# charger_v3_1.net
KiCad netlist of a schematic drawn in EAGLE
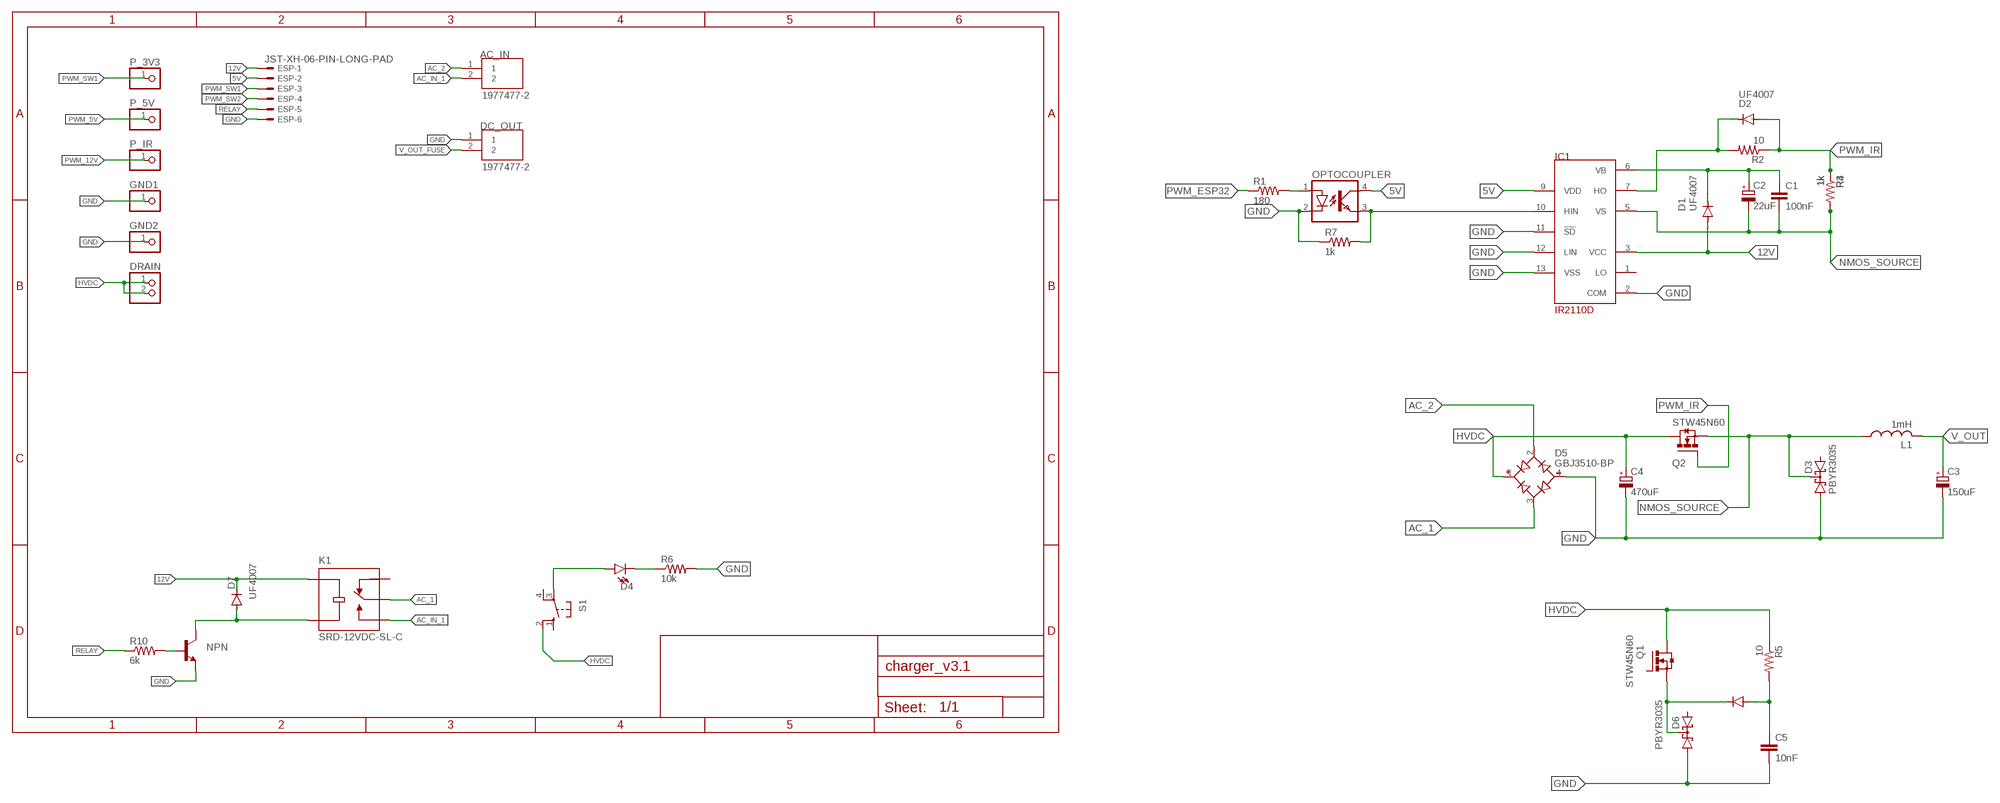
[diagram p0: schematic, sheet 1]

(export (version "E")
  (design (tool "Eeschema 10.0.6"))
  (components
    (comp (ref "AC_IN")
      (value "1977477-2")
      (footprint "eagle-import:TE_1977477-2")
      (fields (field (name "MF") "TE Connectivity"))
      (libsource (lib "eagle-import") (part "1977477-2"))
    )
    (comp (ref "C1")
      (value "100nF")
      (footprint "eagle-import:C025-025X050")
      (libsource (lib "eagle-import") (part "C-EU025-025X050"))
    )
    (comp (ref "C2")
      (value "22uF")
      (footprint "eagle-import:E2,5-6E")
      (libsource (lib "eagle-import") (part "CPOL-EUE2,5-6E"))
    )
    (comp (ref "C3")
      (value "150uF")
      (footprint "eagle-import:E7,5-18")
      (libsource (lib "eagle-import") (part "CPOL-EUE7.5-18"))
    )
    (comp (ref "C4")
      (value "470uF")
      (footprint "eagle-import:EB35D")
      (libsource (lib "eagle-import") (part "CPOL-EUE10-35"))
    )
    (comp (ref "C5")
      (value "10nF")
      (footprint "eagle-import:C025-025X050")
      (libsource (lib "eagle-import") (part "C-EU025-025X050"))
    )
    (comp (ref "D1")
      (value "UF4007")
      (footprint "eagle-import:DO34-7")
      (libsource (lib "eagle-import") (part "BAS15"))
    )
    (comp (ref "D2")
      (value "UF4007")
      (footprint "eagle-import:DO34-7")
      (libsource (lib "eagle-import") (part "BAS15"))
    )
    (comp (ref "D3")
      (value "PBYR3035")
      (footprint "eagle-import:SOT93S")
      (libsource (lib "eagle-import") (part "PBYR3035"))
    )
    (comp (ref "D4")
      (value "LED5MM")
      (footprint "eagle-import:LED_5MM")
      (libsource (lib "eagle-import") (part "LED5MM"))
    )
    (comp (ref "D5")
      (value "GBJ3510-BP")
      (footprint "eagle-import:DIOB_GBJ3510-BP")
      (fields (field (name "MF") "Micro Commercial"))
      (libsource (lib "eagle-import") (part "GBJ3510-BP"))
    )
    (comp (ref "D6")
      (value "PBYR3035")
      (footprint "eagle-import:SOT93S")
      (libsource (lib "eagle-import") (part "PBYR3035"))
    )
    (comp (ref "D7")
      (value "UF4007")
      (footprint "eagle-import:DO34-7")
      (libsource (lib "eagle-import") (part "BAS15"))
    )
    (comp (ref "D8")
      (value "1N4148DO35-7")
      (footprint "eagle-import:DO35-7")
      (libsource (lib "eagle-import") (part "1N4148DO35-7"))
    )
    (comp (ref "DC_OUT")
      (value "1977477-2")
      (footprint "eagle-import:TE_1977477-2")
      (fields (field (name "MF") "TE Connectivity"))
      (libsource (lib "eagle-import") (part "1977477-2"))
    )
    (comp (ref "DRAIN")
      (value "PINHD-1X2")
      (footprint "eagle-import:1X02")
      (libsource (lib "eagle-import") (part "PINHD-1X2"))
    )
    (comp (ref "ESP")
      (value "JST-XH-06-PIN-LONG-PAD")
      (footprint "eagle-import:JST-XH-06-PACKAGE-LONG-PAD")
      (libsource (lib "eagle-import") (part "JST-XH-06-PIN-LONG-PAD"))
    )
    (comp (ref "GND1")
      (value "PINHD-1X1")
      (footprint "eagle-import:1X01")
      (libsource (lib "eagle-import") (part "PINHD-1X1"))
    )
    (comp (ref "GND2")
      (value "PINHD-1X1")
      (footprint "eagle-import:1X01")
      (libsource (lib "eagle-import") (part "PINHD-1X1"))
    )
    (comp (ref "IC1")
      (value "IR2110D")
      (footprint "eagle-import:DIL14")
      (libsource (lib "eagle-import") (part "IR2110D"))
    )
    (comp (ref "K1")
      (value "SRD-12VDC-SL-C")
      (footprint "eagle-import:RELAY_SRD-12VDC-SL-C")
      (fields (field (name "MF") "Songle Relay"))
      (libsource (lib "eagle-import") (part "SRD-12VDC-SL-C"))
    )
    (comp (ref "L1")
      (value "1mH")
      (footprint "eagle-import:TJ7-U1")
      (libsource (lib "eagle-import") (part "L-USTJ7-U1"))
    )
    (comp (ref "NPN")
      (value "BC547A-NPN-TO92-CBE")
      (footprint "eagle-import:TO92-CBE")
      (libsource (lib "eagle-import") (part "-NPN-TO92-CBEBC547A"))
    )
    (comp (ref "OPTOCOUPLER")
      (value "SFH618A-5")
      (footprint "eagle-import:DIP4")
      (fields (field (name "MF") "VISHAY/TELEFUNKEN"))
      (libsource (lib "eagle-import") (part "SFH618?A-5"))
    )
    (comp (ref "P_3V3")
      (value "PINHD-1X1")
      (footprint "eagle-import:1X01")
      (libsource (lib "eagle-import") (part "PINHD-1X1"))
    )
    (comp (ref "P_5V")
      (value "PINHD-1X1")
      (footprint "eagle-import:1X01")
      (libsource (lib "eagle-import") (part "PINHD-1X1"))
    )
    (comp (ref "P_IR")
      (value "PINHD-1X1")
      (footprint "eagle-import:1X01")
      (libsource (lib "eagle-import") (part "PINHD-1X1"))
    )
    (comp (ref "Q1")
      (value "STW45N60")
      (footprint "eagle-import:TO247AC")
      (fields (field (name "MF") "Vishay Siliconix") (field (name "MP") "IRFP240"))
      (libsource (lib "eagle-import") (part "IRFP240"))
    )
    (comp (ref "Q2")
      (value "STW45N60")
      (footprint "eagle-import:TO247AC")
      (fields (field (name "MF") "Vishay Siliconix") (field (name "MP") "IRFP240"))
      (libsource (lib "eagle-import") (part "IRFP240"))
    )
    (comp (ref "R1")
      (value "180")
      (footprint "eagle-import:0204_7")
      (libsource (lib "eagle-import") (part "R-US_0204/7"))
    )
    (comp (ref "R2")
      (value "10")
      (footprint "eagle-import:0204_7")
      (libsource (lib "eagle-import") (part "R-US_0204/7"))
    )
    (comp (ref "R3")
      (value "1k")
      (footprint "eagle-import:0204_7")
      (libsource (lib "eagle-import") (part "R-US_0204/7"))
    )
    (comp (ref "R4")
      (value "1k")
      (footprint "eagle-import:0204_7")
      (libsource (lib "eagle-import") (part "R-US_0204/7"))
    )
    (comp (ref "R5")
      (value "10")
      (footprint "eagle-import:0204_7")
      (libsource (lib "eagle-import") (part "R-US_0204/7"))
    )
    (comp (ref "R6")
      (value "10k")
      (footprint "eagle-import:0204_7")
      (libsource (lib "eagle-import") (part "R-US_0204/7"))
    )
    (comp (ref "R7")
      (value "1k")
      (footprint "eagle-import:0204_7")
      (libsource (lib "eagle-import") (part "R-US_0204/7"))
    )
    (comp (ref "R10")
      (value "6k")
      (footprint "eagle-import:0204_7")
      (libsource (lib "eagle-import") (part "R-US_0204/7"))
    )
    (comp (ref "S1")
      (value "10-XX")
      (footprint "eagle-import:B3F-10XX")
      (fields (field (name "MPN") "B3F-1000"))
      (libsource (lib "eagle-import") (part "10-XX"))
    )
  )
  (nets
    (net (code "1") (name "5V") (class "Default")
      (node (ref "ESP") (pin "2") (pinfunction "S_2") (pintype "passive"))
      (node (ref "IC1") (pin "9") (pinfunction "VDD_9") (pintype "power_in"))
      (node (ref "OPTOCOUPLER") (pin "4") (pinfunction "COL_4") (pintype "passive"))
    )
    (net (code "2") (name "12V") (class "Default")
      (node (ref "D1") (pin "A") (pinfunction "A_A") (pintype "passive"))
      (node (ref "D7") (pin "C") (pinfunction "C_C") (pintype "passive"))
      (node (ref "ESP") (pin "1") (pinfunction "S_1") (pintype "passive"))
      (node (ref "IC1") (pin "3") (pinfunction "VCC_3") (pintype "power_in"))
      (node (ref "K1") (pin "COIL1") (pinfunction "COIL1_COIL1") (pintype "passive"))
    )
    (net (code "3") (name "AC_1") (class "Default")
      (node (ref "D5") (pin "3") (pinfunction "AC2_3") (pintype "passive"))
      (node (ref "K1") (pin "COM") (pinfunction "COM_COM") (pintype "passive"))
    )
    (net (code "4") (name "AC_2") (class "Default")
      (node (ref "AC_IN") (pin "1") (pinfunction "1_1") (pintype "passive"))
      (node (ref "D5") (pin "2") (pinfunction "AC1_2") (pintype "passive"))
    )
    (net (code "5") (name "AC_IN_1") (class "Default")
      (node (ref "AC_IN") (pin "2") (pinfunction "2_2") (pintype "passive"))
      (node (ref "K1") (pin "NO") (pinfunction "NO_NO") (pintype "passive"))
    )
    (net (code "6") (name "GND") (class "Default")
      (node (ref "C3") (pin "-") (pinfunction "-_-") (pintype "passive"))
      (node (ref "C4") (pin "-") (pinfunction "-_-") (pintype "passive"))
      (node (ref "D3") (pin "A1") (pinfunction "A1_A1") (pintype "passive"))
      (node (ref "D5") (pin "4") (pinfunction "-_4") (pintype "passive"))
      (node (ref "DC_OUT") (pin "1") (pinfunction "1_1") (pintype "passive"))
      (node (ref "ESP") (pin "6") (pinfunction "S_6") (pintype "passive"))
      (node (ref "GND1") (pin "1") (pinfunction "1_1") (pintype "passive"))
      (node (ref "GND2") (pin "1") (pinfunction "1_1") (pintype "passive"))
      (node (ref "IC1") (pin "11") (pinfunction "~{SD}_11") (pintype "input"))
      (node (ref "IC1") (pin "12") (pinfunction "LIN_12") (pintype "input"))
      (node (ref "IC1") (pin "13") (pinfunction "VSS_13") (pintype "power_in"))
      (node (ref "IC1") (pin "2") (pinfunction "COM_2") (pintype "power_in"))
      (node (ref "NPN") (pin "E") (pinfunction "E_E") (pintype "passive"))
      (node (ref "OPTOCOUPLER") (pin "2") (pinfunction "C_2") (pintype "passive"))
      (node (ref "R6") (pin "2") (pinfunction "2_2") (pintype "passive"))
      (node (ref "R7") (pin "1") (pinfunction "1_1") (pintype "passive"))
    )
    (net (code "7") (name "HVDC") (class "Default")
      (node (ref "C4") (pin "+") (pinfunction "+_+") (pintype "passive"))
      (node (ref "D5") (pin "1") (pinfunction "+_1") (pintype "passive"))
      (node (ref "DRAIN") (pin "1") (pinfunction "1_1") (pintype "passive"))
      (node (ref "DRAIN") (pin "2") (pinfunction "2_2") (pintype "passive"))
      (node (ref "Q2") (pin "2") (pinfunction "D_2") (pintype "passive"))
      (node (ref "S1") (pin "2") (pinfunction "S1_2") (pintype "passive"))
    )
    (net (code "8") (name "NMOS_SOURCE") (class "Default")
      (node (ref "C1") (pin "2") (pinfunction "2_2") (pintype "passive"))
      (node (ref "C2") (pin "-") (pinfunction "-_-") (pintype "passive"))
      (node (ref "D3") (pin "C") (pinfunction "C_C") (pintype "passive"))
      (node (ref "IC1") (pin "5") (pinfunction "VS_5") (pintype "power_in"))
      (node (ref "L1") (pin "1") (pinfunction "1_1") (pintype "passive"))
      (node (ref "Q2") (pin "3") (pinfunction "S_3") (pintype "passive"))
      (node (ref "R3") (pin "2") (pinfunction "2_2") (pintype "passive"))
      (node (ref "R4") (pin "2") (pinfunction "2_2") (pintype "passive"))
    )
    (net (code "9") (name "Net-(C5-Pad1)") (class "Default")
      (node (ref "C5") (pin "1") (pinfunction "1_1") (pintype "passive"))
      (node (ref "D8") (pin "A") (pinfunction "A_A") (pintype "passive"))
      (node (ref "R5") (pin "2") (pinfunction "2_2") (pintype "passive"))
    )
    (net (code "10") (name "Net-(C5-Pad2)") (class "Default")
      (node (ref "C5") (pin "2") (pinfunction "2_2") (pintype "passive"))
      (node (ref "D6") (pin "A1") (pinfunction "A1_A1") (pintype "passive"))
    )
    (net (code "11") (name "Net-(D4-C)") (class "Default")
      (node (ref "D4") (pin "K") (pinfunction "C_K") (pintype "passive"))
      (node (ref "R6") (pin "1") (pinfunction "1_1") (pintype "passive"))
    )
    (net (code "12") (name "Net-(D7-PadA)") (class "Default")
      (node (ref "D7") (pin "A") (pinfunction "A_A") (pintype "passive"))
      (node (ref "K1") (pin "COIL2") (pinfunction "COIL2_COIL2") (pintype "passive"))
      (node (ref "NPN") (pin "C") (pinfunction "C_C") (pintype "passive"))
    )
    (net (code "13") (name "Net-(IC1-HO)") (class "Default")
      (node (ref "D2") (pin "C") (pinfunction "C_C") (pintype "passive"))
      (node (ref "IC1") (pin "7") (pinfunction "HO_7") (pintype "output"))
      (node (ref "R2") (pin "2") (pinfunction "2_2") (pintype "passive"))
    )
    (net (code "14") (name "Net-(IC1-VB)") (class "Default")
      (node (ref "C1") (pin "1") (pinfunction "1_1") (pintype "passive"))
      (node (ref "C2") (pin "+") (pinfunction "+_+") (pintype "passive"))
      (node (ref "D1") (pin "C") (pinfunction "C_C") (pintype "passive"))
      (node (ref "IC1") (pin "6") (pinfunction "VB_6") (pintype "power_in"))
    )
    (net (code "15") (name "Net-(NPN-PadB)") (class "Default")
      (node (ref "NPN") (pin "B") (pinfunction "B_B") (pintype "passive"))
      (node (ref "R10") (pin "2") (pinfunction "2_2") (pintype "passive"))
    )
    (net (code "16") (name "Net-(OPTOCOUPLER-A)") (class "Default")
      (node (ref "OPTOCOUPLER") (pin "1") (pinfunction "A_1") (pintype "passive"))
      (node (ref "R1") (pin "2") (pinfunction "2_2") (pintype "passive"))
    )
    (net (code "17") (name "Net-(Q1-D)") (class "Default")
      (node (ref "Q1") (pin "2") (pinfunction "D_2") (pintype "passive"))
      (node (ref "R5") (pin "1") (pinfunction "1_1") (pintype "passive"))
    )
    (net (code "18") (name "Net-(Q1-S)") (class "Default")
      (node (ref "D6") (pin "C") (pinfunction "C_C") (pintype "passive"))
      (node (ref "D8") (pin "C") (pinfunction "C_C") (pintype "passive"))
      (node (ref "Q1") (pin "3") (pinfunction "S_3") (pintype "passive"))
    )
    (net (code "19") (name "Net-(S1-P)") (class "Default")
      (node (ref "D4") (pin "A") (pinfunction "A_A") (pintype "passive"))
      (node (ref "S1") (pin "3") (pinfunction "P_3") (pintype "passive"))
    )
    (net (code "20") (name "PWM_5V") (class "Default")
      (node (ref "IC1") (pin "10") (pinfunction "HIN_10") (pintype "input"))
      (node (ref "OPTOCOUPLER") (pin "3") (pinfunction "EMIT_3") (pintype "passive"))
      (node (ref "P_5V") (pin "1") (pinfunction "1_1") (pintype "passive"))
      (node (ref "R7") (pin "2") (pinfunction "2_2") (pintype "passive"))
    )
    (net (code "21") (name "PWM_12V") (class "Default")
      (node (ref "P_IR") (pin "1") (pinfunction "1_1") (pintype "passive"))
    )
    (net (code "22") (name "PWM_ESP32") (class "Default")
      (node (ref "R1") (pin "1") (pinfunction "1_1") (pintype "passive"))
    )
    (net (code "23") (name "PWM_IR") (class "Default")
      (node (ref "D2") (pin "A") (pinfunction "A_A") (pintype "passive"))
      (node (ref "Q2") (pin "1") (pinfunction "G_1") (pintype "passive"))
      (node (ref "R2") (pin "1") (pinfunction "1_1") (pintype "passive"))
      (node (ref "R3") (pin "1") (pinfunction "1_1") (pintype "passive"))
      (node (ref "R4") (pin "1") (pinfunction "1_1") (pintype "passive"))
    )
    (net (code "24") (name "PWM_SW1") (class "Default")
      (node (ref "ESP") (pin "3") (pinfunction "S_3") (pintype "passive"))
      (node (ref "P_3V3") (pin "1") (pinfunction "1_1") (pintype "passive"))
    )
    (net (code "25") (name "PWM_SW2") (class "Default")
      (node (ref "ESP") (pin "4") (pinfunction "S_4") (pintype "passive"))
    )
    (net (code "26") (name "RELAY") (class "Default")
      (node (ref "ESP") (pin "5") (pinfunction "S_5") (pintype "passive"))
      (node (ref "R10") (pin "1") (pinfunction "1_1") (pintype "passive"))
    )
    (net (code "27") (name "V_OUT") (class "Default")
      (node (ref "C3") (pin "+") (pinfunction "+_+") (pintype "passive"))
      (node (ref "L1") (pin "2") (pinfunction "2_2") (pintype "passive"))
    )
    (net (code "28") (name "V_OUT_FUSE") (class "Default")
      (node (ref "DC_OUT") (pin "2") (pinfunction "2_2") (pintype "passive"))
    )
    (net (code "29") (name "unconnected-(D3-PadA2)") (class "Default")
      (node (ref "D3") (pin "A2") (pinfunction "A2_A2") (pintype "passive"))
    )
    (net (code "30") (name "unconnected-(D6-PadA2)") (class "Default")
      (node (ref "D6") (pin "A2") (pinfunction "A2_A2") (pintype "passive"))
    )
    (net (code "31") (name "unconnected-(IC1-LO-Pad1)") (class "Default")
      (node (ref "IC1") (pin "1") (pinfunction "LO_1") (pintype "output"))
    )
    (net (code "32") (name "unconnected-(K1-PadNC)") (class "Default")
      (node (ref "K1") (pin "NC") (pinfunction "NC_NC") (pintype "passive"))
    )
    (net (code "33") (name "unconnected-(Q1-G-Pad1)") (class "Default")
      (node (ref "Q1") (pin "1") (pinfunction "G_1") (pintype "passive"))
    )
    (net (code "34") (name "unconnected-(S1-P1-Pad4)") (class "Default")
      (node (ref "S1") (pin "4") (pinfunction "P1_4") (pintype "passive"))
    )
    (net (code "35") (name "unconnected-(S1-S-Pad1)") (class "Default")
      (node (ref "S1") (pin "1") (pinfunction "S_1") (pintype "passive"))
    )
  )
)
